# mainboard.net
KiCad netlist of a schematic drawn in Altium Designer
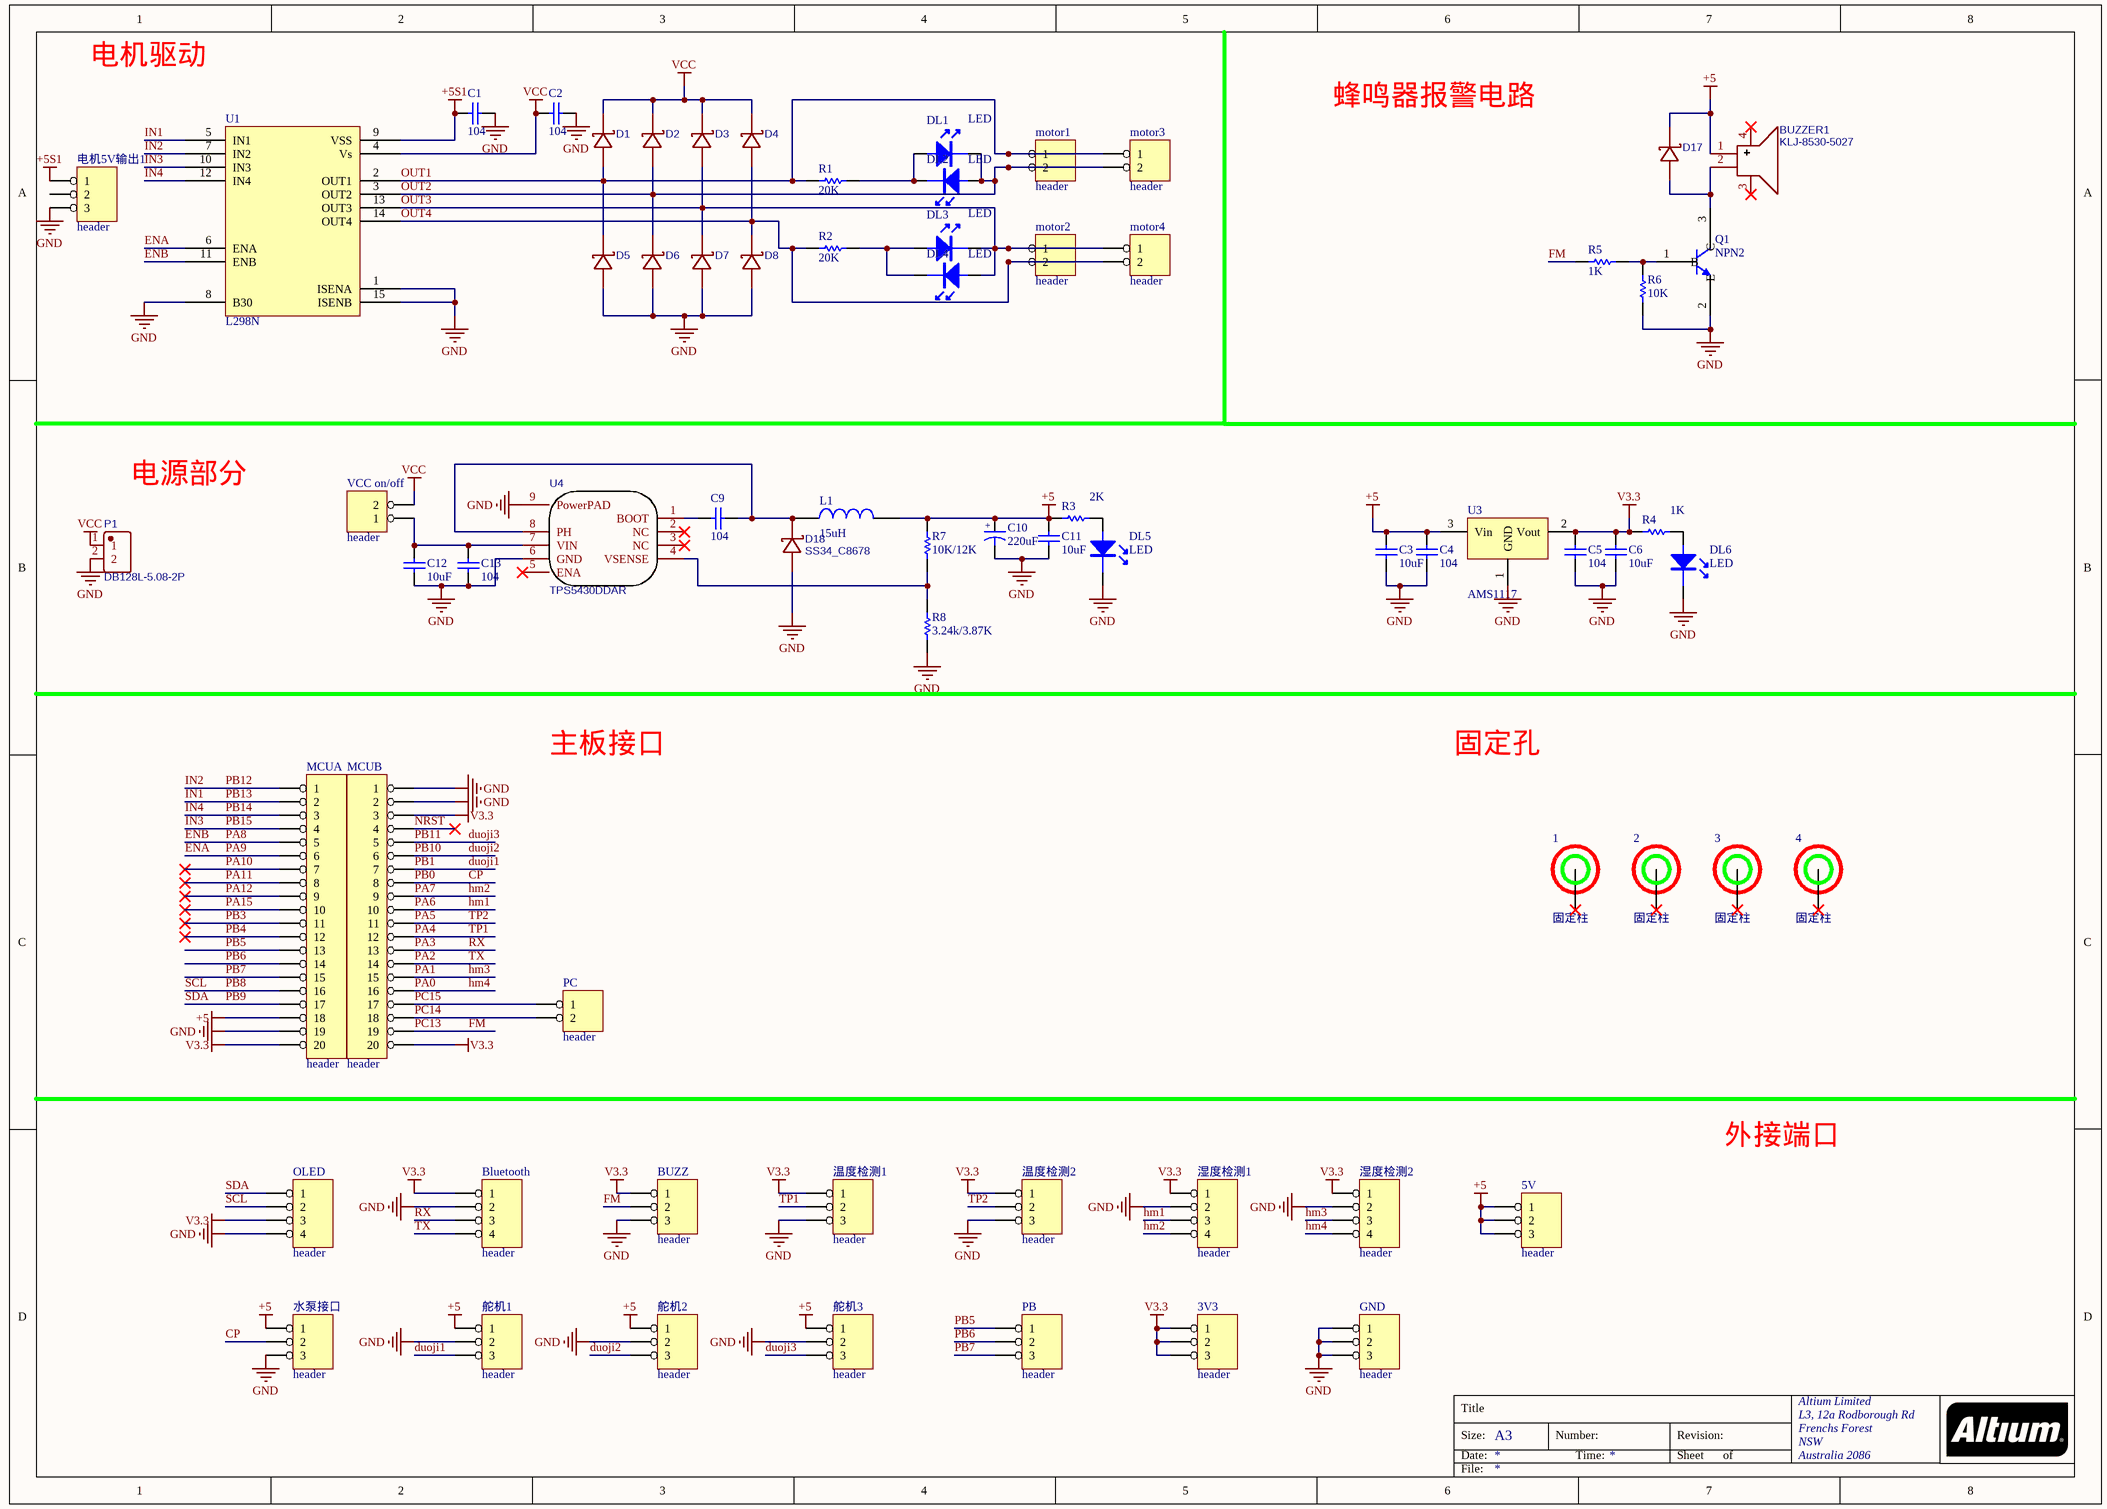
[diagram p0: mainboard.SchDoc]

(export (version "E")
  (design (tool "Eeschema 10.0.6"))
  (components
    (comp (ref "1") (value "固定柱") (footprint "M3x4+6_L") (libsource (lib "My Footprint") (part "M3*10 固定柱")))
    (comp (ref "2") (value "固定柱") (footprint "M3x4+6_L") (libsource (lib "My Footprint") (part "M3*10 固定柱")))
    (comp (ref "3") (value "固定柱") (footprint "M3x4+6_L") (libsource (lib "My Footprint") (part "M3*10 固定柱")))
    (comp (ref "3V3")
      (value "header")
      (footprint "header3")
      (libsource (lib "My Footprint") (part "HEADER 3"))
    )
    (comp (ref "4") (value "固定柱") (footprint "M3x4+6_L") (libsource (lib "My Footprint") (part "M3*10 固定柱")))
    (comp (ref "5V")
      (value "header")
      (footprint "header3")
      (libsource (lib "My Footprint") (part "HEADER 3"))
    )
    (comp (ref "Bluetooth")
      (value "header")
      (footprint "header4")
      (libsource (lib "My Footprint") (part "HEADER 4"))
    )
    (comp (ref "BUZZ")
      (value "header")
      (footprint "header3")
      (libsource (lib "My Footprint") (part "HEADER 3"))
    )
    (comp (ref "BUZZER1")
      (value "KLJ-8530-5027")
      (footprint "BUZ-SMD_4P-L8.5-W8.5-TL")
      (fields (field (name "BOM_SUPPLIER PART") "C556938") (field (name "CONTRIBUTOR") "LCSC"))
      (libsource (lib "My Footprint") (part "BUZZ"))
    )
    (comp (ref "C1")
      (value "104")
      (footprint "0603_C")
      (description "Capacitor")
      (fields (field (name "PUBLISHER") "Altium Limited"))
      (libsource (lib "My Footprint") (part "CAP"))
    )
    (comp (ref "C2")
      (value "104")
      (footprint "0603_C")
      (description "Capacitor")
      (fields (field (name "PUBLISHER") "Altium Limited"))
      (libsource (lib "My Footprint") (part "CAP"))
    )
    (comp (ref "C3")
      (value "10uF")
      (footprint "0603_C")
      (description "Capacitor")
      (fields (field (name "PUBLISHER") "Altium Limited"))
      (libsource (lib "My Footprint") (part "CAP"))
    )
    (comp (ref "C4")
      (value "104")
      (footprint "0603_C")
      (description "Capacitor")
      (fields (field (name "PUBLISHER") "Altium Limited"))
      (libsource (lib "My Footprint") (part "CAP"))
    )
    (comp (ref "C5")
      (value "104")
      (footprint "0603_C")
      (description "Capacitor")
      (fields (field (name "PUBLISHER") "Altium Limited"))
      (libsource (lib "My Footprint") (part "CAP"))
    )
    (comp (ref "C6")
      (value "10uF")
      (footprint "0603_C")
      (description "Capacitor")
      (fields (field (name "PUBLISHER") "Altium Limited"))
      (libsource (lib "My Footprint") (part "CAP"))
    )
    (comp (ref "C9")
      (value "104")
      (footprint "0603_C")
      (description "Capacitor")
      (fields (field (name "PUBLISHER") "Altium Limited"))
      (libsource (lib "My Footprint") (part "CAP"))
    )
    (comp (ref "C10") (value "220uF") (footprint "CD7") (libsource (lib "My Footprint") (part "CAP1")))
    (comp (ref "C11")
      (value "10uF")
      (footprint "0805_c")
      (description "Capacitor")
      (fields (field (name "PUBLISHER") "Altium Limited"))
      (libsource (lib "My Footprint") (part "CAP"))
    )
    (comp (ref "C12")
      (value "10uF")
      (footprint "0805_c")
      (description "Capacitor")
      (fields (field (name "PUBLISHER") "Altium Limited"))
      (libsource (lib "My Footprint") (part "CAP"))
    )
    (comp (ref "C13")
      (value "104")
      (footprint "0603_C")
      (description "Capacitor")
      (fields (field (name "PUBLISHER") "Altium Limited"))
      (libsource (lib "My Footprint") (part "CAP"))
    )
    (comp (ref "D1")
      (value "~")
      (footprint "DO-214AC_L4.3-W2.7-LS5.3-RD")
      (fields (field (name "BOM_MANUFACTURER PART") "SS34") (field (name "BOM_SUPPLIER PART") "C8678"))
      (libsource (lib "My Footprint") (part "SS34_C8678"))
    )
    (comp (ref "D2")
      (value "~")
      (footprint "DO-214AC_L4.3-W2.7-LS5.3-RD")
      (fields (field (name "BOM_MANUFACTURER PART") "SS34") (field (name "BOM_SUPPLIER PART") "C8678"))
      (libsource (lib "My Footprint") (part "SS34_C8678"))
    )
    (comp (ref "D3")
      (value "~")
      (footprint "DO-214AC_L4.3-W2.7-LS5.3-RD")
      (fields (field (name "BOM_MANUFACTURER PART") "SS34") (field (name "BOM_SUPPLIER PART") "C8678"))
      (libsource (lib "My Footprint") (part "SS34_C8678"))
    )
    (comp (ref "D4")
      (value "~")
      (footprint "DO-214AC_L4.3-W2.7-LS5.3-RD")
      (fields (field (name "BOM_MANUFACTURER PART") "SS34") (field (name "BOM_SUPPLIER PART") "C8678"))
      (libsource (lib "My Footprint") (part "SS34_C8678"))
    )
    (comp (ref "D5")
      (value "~")
      (footprint "DO-214AC_L4.3-W2.7-LS5.3-RD")
      (fields (field (name "BOM_MANUFACTURER PART") "SS34") (field (name "BOM_SUPPLIER PART") "C8678"))
      (libsource (lib "My Footprint") (part "SS34_C8678"))
    )
    (comp (ref "D6")
      (value "~")
      (footprint "DO-214AC_L4.3-W2.7-LS5.3-RD")
      (fields (field (name "BOM_MANUFACTURER PART") "SS34") (field (name "BOM_SUPPLIER PART") "C8678"))
      (libsource (lib "My Footprint") (part "SS34_C8678"))
    )
    (comp (ref "D7")
      (value "~")
      (footprint "DO-214AC_L4.3-W2.7-LS5.3-RD")
      (fields (field (name "BOM_MANUFACTURER PART") "SS34") (field (name "BOM_SUPPLIER PART") "C8678"))
      (libsource (lib "My Footprint") (part "SS34_C8678"))
    )
    (comp (ref "D8")
      (value "~")
      (footprint "DO-214AC_L4.3-W2.7-LS5.3-RD")
      (fields (field (name "BOM_MANUFACTURER PART") "SS34") (field (name "BOM_SUPPLIER PART") "C8678"))
      (libsource (lib "My Footprint") (part "SS34_C8678"))
    )
    (comp (ref "D17")
      (value "~")
      (footprint "DO-214AC_L4.3-W2.7-LS5.3-RD")
      (fields (field (name "BOM_MANUFACTURER PART") "SS34") (field (name "BOM_SUPPLIER PART") "C8678"))
      (libsource (lib "My Footprint") (part "SS34_C8678"))
    )
    (comp (ref "D18")
      (value "SS34_C8678")
      (footprint "DO-214AC_L4.3-W2.7-LS5.3-RD")
      (fields (field (name "BOM_MANUFACTURER PART") "SS34") (field (name "BOM_SUPPLIER PART") "C8678"))
      (libsource (lib "My Footprint") (part "SS34_C8678"))
    )
    (comp (ref "DL1")
      (value "LED")
      (footprint "0805_LED")
      (description "LED 发光二极管")
      (libsource (lib "My Footprint") (part "LED"))
    )
    (comp (ref "DL2")
      (value "LED")
      (footprint "0805_LED")
      (description "LED 发光二极管")
      (libsource (lib "My Footprint") (part "LED"))
    )
    (comp (ref "DL3")
      (value "LED")
      (footprint "0805_LED")
      (description "LED 发光二极管")
      (libsource (lib "My Footprint") (part "LED"))
    )
    (comp (ref "DL4")
      (value "LED")
      (footprint "0805_LED")
      (description "LED 发光二极管")
      (libsource (lib "My Footprint") (part "LED"))
    )
    (comp (ref "DL5")
      (value "LED")
      (footprint "0805_LED")
      (description "LED 发光二极管")
      (libsource (lib "My Footprint") (part "LED"))
    )
    (comp (ref "DL6")
      (value "LED")
      (footprint "0805_LED")
      (description "LED 发光二极管")
      (libsource (lib "My Footprint") (part "LED"))
    )
    (comp (ref "GND")
      (value "header")
      (footprint "header3")
      (libsource (lib "My Footprint") (part "HEADER 3"))
    )
    (comp (ref "L1")
      (value "15uH")
      (footprint "CD75")
      (description "INDUCTOR")
      (libsource (lib "电感") (part "INDUCTOR"))
    )
    (comp (ref "MCUA")
      (value "header")
      (footprint "header20")
      (libsource (lib "My Footprint") (part "HEADER 20"))
    )
    (comp (ref "MCUB") (value "header") (footprint "header20") (libsource (lib "") (part "HEADER 20_1")))
    (comp (ref "motor1")
      (value "header")
      (footprint "header2")
      (libsource (lib "My Footprint") (part "HEADER 2"))
    )
    (comp (ref "motor2")
      (value "header")
      (footprint "header2")
      (libsource (lib "My Footprint") (part "HEADER 2"))
    )
    (comp (ref "motor3")
      (value "header")
      (footprint "header2")
      (libsource (lib "My Footprint") (part "HEADER 2"))
    )
    (comp (ref "motor4")
      (value "header")
      (footprint "header2")
      (libsource (lib "My Footprint") (part "HEADER 2"))
    )
    (comp (ref "OLED")
      (value "header")
      (footprint "header4")
      (libsource (lib "My Footprint") (part "HEADER 4"))
    )
    (comp (ref "P1")
      (value "DB128L-5.08-2P")
      (footprint "CONN-TH_2P-P5.08_DB128L-5.08-2P")
      (fields (field (name "BOM_SUPPLIER PART") "C395868") (field (name "CONTRIBUTOR") "LCSC"))
      (libsource (lib "My Footprint") (part "duanzi-5.08-2P"))
    )
    (comp (ref "PB")
      (value "header")
      (footprint "header3")
      (libsource (lib "My Footprint") (part "HEADER 3"))
    )
    (comp (ref "PC")
      (value "header")
      (footprint "header2")
      (libsource (lib "My Footprint") (part "HEADER 2"))
    )
    (comp (ref "Q1")
      (value "NPN2")
      (footprint "SOT-23-3")
      (description "贴片")
      (libsource (lib "My Footprint") (part "NPN2"))
    )
    (comp (ref "R1")
      (value "20K")
      (footprint "0603_R")
      (description "Resistor")
      (fields (field (name "PUBLISHER") "Altium Limited"))
      (libsource (lib "My Footprint") (part "RES"))
    )
    (comp (ref "R2")
      (value "20K")
      (footprint "0603_R")
      (description "Resistor")
      (fields (field (name "PUBLISHER") "Altium Limited"))
      (libsource (lib "My Footprint") (part "RES"))
    )
    (comp (ref "R3")
      (value "2K")
      (footprint "0805_r")
      (description "Resistor")
      (fields (field (name "PUBLISHER") "Altium Limited"))
      (libsource (lib "My Footprint") (part "RES"))
    )
    (comp (ref "R4")
      (value "1K")
      (footprint "0805_r")
      (description "Resistor")
      (fields (field (name "PUBLISHER") "Altium Limited"))
      (libsource (lib "My Footprint") (part "RES"))
    )
    (comp (ref "R5")
      (value "1K")
      (footprint "0805_r")
      (description "Resistor")
      (fields (field (name "PUBLISHER") "Altium Limited"))
      (libsource (lib "My Footprint") (part "RES"))
    )
    (comp (ref "R6")
      (value "10K")
      (footprint "0805_r")
      (description "Resistor")
      (fields (field (name "PUBLISHER") "Altium Limited"))
      (libsource (lib "My Footprint") (part "RES"))
    )
    (comp (ref "R7")
      (value "10K/12K")
      (footprint "0805_r")
      (description "Resistor")
      (fields (field (name "PUBLISHER") "Altium Limited"))
      (libsource (lib "My Footprint") (part "RES"))
    )
    (comp (ref "R8")
      (value "3.24k/3.87K")
      (footprint "0805_r")
      (description "Resistor")
      (fields (field (name "PUBLISHER") "Altium Limited"))
      (libsource (lib "My Footprint") (part "RES"))
    )
    (comp (ref "U1") (value "L298N") (footprint "L298N") (libsource (lib "My Footprint") (part "L298N")))
    (comp (ref "U3")
      (value "AMS1117")
      (footprint "SOT-223")
      (description "3.3V电压转换器AMS1117")
      (libsource (lib "My Footprint") (part "AMS1117"))
    )
    (comp (ref "U4")
      (value "TPS5430DDAR")
      (footprint "SOIC-8_L5.0-W4.0-P1.27-LS6.0-BL-EP")
      (fields (field (name "BOM_SUPPLIER PART") "C9864"))
      (libsource (lib "My Footprint") (part "TPS5430DDAR"))
    )
    (comp (ref "VCC on/off") (value "header") (footprint "header2") (libsource (lib "") (part "HEADER 2_1")))
    (comp (ref "水泵接口")
      (value "header")
      (footprint "header3")
      (libsource (lib "My Footprint") (part "HEADER 3"))
    )
    (comp (ref "温度检测1")
      (value "header")
      (footprint "header3")
      (libsource (lib "My Footprint") (part "HEADER 3"))
    )
    (comp (ref "温度检测2")
      (value "header")
      (footprint "header3")
      (libsource (lib "My Footprint") (part "HEADER 3"))
    )
    (comp (ref "湿度检测1")
      (value "header")
      (footprint "header4")
      (libsource (lib "My Footprint") (part "HEADER 4"))
    )
    (comp (ref "湿度检测2")
      (value "header")
      (footprint "header4")
      (libsource (lib "My Footprint") (part "HEADER 4"))
    )
    (comp (ref "电机5V输出1")
      (value "header")
      (footprint "header3")
      (libsource (lib "My Footprint") (part "HEADER 3"))
    )
    (comp (ref "舵机1")
      (value "header")
      (footprint "header3")
      (libsource (lib "My Footprint") (part "HEADER 3"))
    )
    (comp (ref "舵机2")
      (value "header")
      (footprint "header3")
      (libsource (lib "My Footprint") (part "HEADER 3"))
    )
    (comp (ref "舵机3")
      (value "header")
      (footprint "header3")
      (libsource (lib "My Footprint") (part "HEADER 3"))
    )
  )
  (nets
    (net (code "1") (name "+5") (class "Default")
      (node (ref "5V") (pin "1") (pinfunction "1_1") (pintype "passive"))
      (node (ref "5V") (pin "2") (pinfunction "2_2") (pintype "passive"))
      (node (ref "5V") (pin "3") (pinfunction "3_3") (pintype "passive"))
      (node (ref "BUZZER1") (pin "1") (pinfunction "+_1") (pintype "passive"))
      (node (ref "C10") (pin "1") (pinfunction "1_1") (pintype "passive"))
      (node (ref "C11") (pin "2") (pinfunction "2_2") (pintype "passive"))
      (node (ref "C3") (pin "2") (pinfunction "2_2") (pintype "passive"))
      (node (ref "C4") (pin "2") (pinfunction "2_2") (pintype "passive"))
      (node (ref "D17") (pin "1") (pinfunction "K_1") (pintype "passive"))
      (node (ref "L1") (pin "2") (pinfunction "2_2") (pintype "passive"))
      (node (ref "MCUA") (pin "18") (pinfunction "18_18") (pintype "passive"))
      (node (ref "R3") (pin "2") (pinfunction "2_2") (pintype "passive"))
      (node (ref "R7") (pin "2") (pinfunction "2_2") (pintype "passive"))
      (node (ref "U3") (pin "3") (pinfunction "Vin_3") (pintype "passive"))
      (node (ref "水泵接口") (pin "1") (pinfunction "1_1") (pintype "passive"))
      (node (ref "舵机1") (pin "1") (pinfunction "1_1") (pintype "passive"))
      (node (ref "舵机2") (pin "1") (pinfunction "1_1") (pintype "passive"))
      (node (ref "舵机3") (pin "1") (pinfunction "1_1") (pintype "passive"))
    )
    (net (code "2") (name "+5S1") (class "Default")
      (node (ref "C1") (pin "1") (pinfunction "1_1") (pintype "passive"))
      (node (ref "U1") (pin "9") (pinfunction "VSS_9") (pintype "passive"))
      (node (ref "电机5V输出1") (pin "1") (pinfunction "1_1") (pintype "passive"))
    )
    (net (code "3") (name "/CP") (class "Default")
      (node (ref "MCUB") (pin "8") (pinfunction "8_8") (pintype "passive"))
      (node (ref "水泵接口") (pin "2") (pinfunction "2_2") (pintype "passive"))
    )
    (net (code "4") (name "/ENA") (class "Default")
      (node (ref "MCUA") (pin "6") (pinfunction "6_6") (pintype "passive"))
      (node (ref "U1") (pin "6") (pinfunction "ENA_6") (pintype "passive"))
    )
    (net (code "5") (name "/ENB") (class "Default")
      (node (ref "MCUA") (pin "5") (pinfunction "5_5") (pintype "passive"))
      (node (ref "U1") (pin "11") (pinfunction "ENB_11") (pintype "passive"))
    )
    (net (code "6") (name "/FM") (class "Default")
      (node (ref "BUZZ") (pin "2") (pinfunction "2_2") (pintype "passive"))
      (node (ref "MCUB") (pin "19") (pinfunction "19_19") (pintype "passive"))
      (node (ref "R5") (pin "1") (pinfunction "1_1") (pintype "passive"))
    )
    (net (code "7") (name "/IN1") (class "Default")
      (node (ref "MCUA") (pin "2") (pinfunction "2_2") (pintype "passive"))
      (node (ref "U1") (pin "5") (pinfunction "IN1_5") (pintype "passive"))
    )
    (net (code "8") (name "/IN2") (class "Default")
      (node (ref "MCUA") (pin "1") (pinfunction "1_1") (pintype "passive"))
      (node (ref "U1") (pin "7") (pinfunction "IN2_7") (pintype "passive"))
    )
    (net (code "9") (name "/IN3") (class "Default")
      (node (ref "MCUA") (pin "4") (pinfunction "4_4") (pintype "passive"))
      (node (ref "U1") (pin "10") (pinfunction "IN3_10") (pintype "passive"))
    )
    (net (code "10") (name "/IN4") (class "Default")
      (node (ref "MCUA") (pin "3") (pinfunction "3_3") (pintype "passive"))
      (node (ref "U1") (pin "12") (pinfunction "IN4_12") (pintype "passive"))
    )
    (net (code "11") (name "/NRST") (class "Default")
      (node (ref "MCUB") (pin "4") (pinfunction "4_4") (pintype "passive+no_connect"))
    )
    (net (code "12") (name "/OUT1") (class "Default")
      (node (ref "D1") (pin "2") (pinfunction "A_2") (pintype "passive"))
      (node (ref "D5") (pin "1") (pinfunction "K_1") (pintype "passive"))
      (node (ref "R1") (pin "1") (pinfunction "1_1") (pintype "passive"))
      (node (ref "U1") (pin "2") (pinfunction "OUT1_2") (pintype "passive"))
      (node (ref "motor1") (pin "1") (pinfunction "1_1") (pintype "passive"))
      (node (ref "motor3") (pin "1") (pinfunction "1_1") (pintype "passive"))
    )
    (net (code "13") (name "/OUT2") (class "Default")
      (node (ref "D2") (pin "2") (pinfunction "A_2") (pintype "passive"))
      (node (ref "D6") (pin "1") (pinfunction "K_1") (pintype "passive"))
      (node (ref "DL1") (pin "2") (pinfunction "K_2") (pintype "passive"))
      (node (ref "DL2") (pin "1") (pinfunction "A_1") (pintype "passive"))
      (node (ref "U1") (pin "3") (pinfunction "OUT2_3") (pintype "passive"))
      (node (ref "motor1") (pin "2") (pinfunction "2_2") (pintype "passive"))
      (node (ref "motor3") (pin "2") (pinfunction "2_2") (pintype "passive"))
    )
    (net (code "14") (name "/OUT3") (class "Default")
      (node (ref "D3") (pin "2") (pinfunction "A_2") (pintype "passive"))
      (node (ref "D7") (pin "1") (pinfunction "K_1") (pintype "passive"))
      (node (ref "DL3") (pin "2") (pinfunction "K_2") (pintype "passive"))
      (node (ref "DL4") (pin "1") (pinfunction "A_1") (pintype "passive"))
      (node (ref "U1") (pin "13") (pinfunction "OUT3_13") (pintype "passive"))
      (node (ref "motor2") (pin "1") (pinfunction "1_1") (pintype "passive"))
      (node (ref "motor4") (pin "1") (pinfunction "1_1") (pintype "passive"))
    )
    (net (code "15") (name "/OUT4") (class "Default")
      (node (ref "D4") (pin "2") (pinfunction "A_2") (pintype "passive"))
      (node (ref "D8") (pin "1") (pinfunction "K_1") (pintype "passive"))
      (node (ref "R2") (pin "1") (pinfunction "1_1") (pintype "passive"))
      (node (ref "U1") (pin "14") (pinfunction "OUT4_14") (pintype "passive"))
      (node (ref "motor2") (pin "2") (pinfunction "2_2") (pintype "passive"))
      (node (ref "motor4") (pin "2") (pinfunction "2_2") (pintype "passive"))
    )
    (net (code "16") (name "/PA0") (class "Default")
      (node (ref "MCUB") (pin "16") (pinfunction "16_16") (pintype "passive"))
      (node (ref "湿度检测2") (pin "4") (pinfunction "4_4") (pintype "passive"))
    )
    (net (code "17") (name "/PA1") (class "Default")
      (node (ref "MCUB") (pin "15") (pinfunction "15_15") (pintype "passive"))
      (node (ref "湿度检测2") (pin "3") (pinfunction "3_3") (pintype "passive"))
    )
    (net (code "18") (name "/PA2") (class "Default")
      (node (ref "Bluetooth") (pin "4") (pinfunction "4_4") (pintype "passive"))
      (node (ref "MCUB") (pin "14") (pinfunction "14_14") (pintype "passive"))
    )
    (net (code "19") (name "/PA3") (class "Default")
      (node (ref "Bluetooth") (pin "3") (pinfunction "3_3") (pintype "passive"))
      (node (ref "MCUB") (pin "13") (pinfunction "13_13") (pintype "passive"))
    )
    (net (code "20") (name "/PA4") (class "Default")
      (node (ref "MCUB") (pin "12") (pinfunction "12_12") (pintype "passive"))
      (node (ref "温度检测1") (pin "2") (pinfunction "2_2") (pintype "passive"))
    )
    (net (code "21") (name "/PA5") (class "Default")
      (node (ref "MCUB") (pin "11") (pinfunction "11_11") (pintype "passive"))
      (node (ref "温度检测2") (pin "2") (pinfunction "2_2") (pintype "passive"))
    )
    (net (code "22") (name "/PA6") (class "Default")
      (node (ref "MCUB") (pin "10") (pinfunction "10_10") (pintype "passive"))
      (node (ref "湿度检测1") (pin "3") (pinfunction "3_3") (pintype "passive"))
    )
    (net (code "23") (name "/PA7") (class "Default")
      (node (ref "MCUB") (pin "9") (pinfunction "9_9") (pintype "passive"))
      (node (ref "湿度检测1") (pin "4") (pinfunction "4_4") (pintype "passive"))
    )
    (net (code "24") (name "/PA10") (class "Default")
      (node (ref "MCUA") (pin "7") (pinfunction "7_7") (pintype "passive+no_connect"))
    )
    (net (code "25") (name "/PA11") (class "Default")
      (node (ref "MCUA") (pin "8") (pinfunction "8_8") (pintype "passive+no_connect"))
    )
    (net (code "26") (name "/PA12") (class "Default")
      (node (ref "MCUA") (pin "9") (pinfunction "9_9") (pintype "passive+no_connect"))
    )
    (net (code "27") (name "/PA15") (class "Default")
      (node (ref "MCUA") (pin "10") (pinfunction "10_10") (pintype "passive+no_connect"))
    )
    (net (code "28") (name "/PB1") (class "Default")
      (node (ref "MCUB") (pin "7") (pinfunction "7_7") (pintype "passive"))
      (node (ref "舵机1") (pin "3") (pinfunction "3_3") (pintype "passive"))
    )
    (net (code "29") (name "/PB3") (class "Default")
      (node (ref "MCUA") (pin "11") (pinfunction "11_11") (pintype "passive+no_connect"))
    )
    (net (code "30") (name "/PB4") (class "Default")
      (node (ref "MCUA") (pin "12") (pinfunction "12_12") (pintype "passive+no_connect"))
    )
    (net (code "31") (name "/PB5") (class "Default")
      (node (ref "MCUA") (pin "13") (pinfunction "13_13") (pintype "passive"))
      (node (ref "PB") (pin "1") (pinfunction "1_1") (pintype "passive"))
    )
    (net (code "32") (name "/PB6") (class "Default")
      (node (ref "MCUA") (pin "14") (pinfunction "14_14") (pintype "passive"))
      (node (ref "PB") (pin "2") (pinfunction "2_2") (pintype "passive"))
    )
    (net (code "33") (name "/PB7") (class "Default")
      (node (ref "MCUA") (pin "15") (pinfunction "15_15") (pintype "passive"))
      (node (ref "PB") (pin "3") (pinfunction "3_3") (pintype "passive"))
    )
    (net (code "34") (name "/PB8") (class "Default")
      (node (ref "MCUA") (pin "16") (pinfunction "16_16") (pintype "passive"))
      (node (ref "OLED") (pin "2") (pinfunction "2_2") (pintype "passive"))
    )
    (net (code "35") (name "/PB9") (class "Default")
      (node (ref "MCUA") (pin "17") (pinfunction "17_17") (pintype "passive"))
      (node (ref "OLED") (pin "1") (pinfunction "1_1") (pintype "passive"))
    )
    (net (code "36") (name "/PB10") (class "Default")
      (node (ref "MCUB") (pin "6") (pinfunction "6_6") (pintype "passive"))
      (node (ref "舵机2") (pin "3") (pinfunction "3_3") (pintype "passive"))
    )
    (net (code "37") (name "/PB11") (class "Default")
      (node (ref "MCUB") (pin "5") (pinfunction "5_5") (pintype "passive"))
      (node (ref "舵机3") (pin "3") (pinfunction "3_3") (pintype "passive"))
    )
    (net (code "38") (name "/PC14") (class "Default")
      (node (ref "MCUB") (pin "18") (pinfunction "18_18") (pintype "passive"))
      (node (ref "PC") (pin "2") (pinfunction "2_2") (pintype "passive"))
    )
    (net (code "39") (name "/PC15") (class "Default")
      (node (ref "MCUB") (pin "17") (pinfunction "17_17") (pintype "passive"))
      (node (ref "PC") (pin "1") (pinfunction "1_1") (pintype "passive"))
    )
    (net (code "40") (name "GND") (class "Default")
      (node (ref "BUZZ") (pin "3") (pinfunction "3_3") (pintype "passive"))
      (node (ref "Bluetooth") (pin "2") (pinfunction "2_2") (pintype "passive"))
      (node (ref "C1") (pin "2") (pinfunction "2_2") (pintype "passive"))
      (node (ref "C10") (pin "2") (pinfunction "2_2") (pintype "passive"))
      (node (ref "C11") (pin "1") (pinfunction "1_1") (pintype "passive"))
      (node (ref "C12") (pin "1") (pinfunction "1_1") (pintype "passive"))
      (node (ref "C13") (pin "1") (pinfunction "1_1") (pintype "passive"))
      (node (ref "C2") (pin "2") (pinfunction "2_2") (pintype "passive"))
      (node (ref "C3") (pin "1") (pinfunction "1_1") (pintype "passive"))
      (node (ref "C4") (pin "1") (pinfunction "1_1") (pintype "passive"))
      (node (ref "C5") (pin "1") (pinfunction "1_1") (pintype "passive"))
      (node (ref "C6") (pin "1") (pinfunction "1_1") (pintype "passive"))
      (node (ref "D18") (pin "2") (pinfunction "A_2") (pintype "passive"))
      (node (ref "D5") (pin "2") (pinfunction "A_2") (pintype "passive"))
      (node (ref "D6") (pin "2") (pinfunction "A_2") (pintype "passive"))
      (node (ref "D7") (pin "2") (pinfunction "A_2") (pintype "passive"))
      (node (ref "D8") (pin "2") (pinfunction "A_2") (pintype "passive"))
      (node (ref "DL5") (pin "2") (pinfunction "K_2") (pintype "passive"))
      (node (ref "DL6") (pin "2") (pinfunction "K_2") (pintype "passive"))
      (node (ref "GND") (pin "1") (pinfunction "1_1") (pintype "passive"))
      (node (ref "GND") (pin "2") (pinfunction "2_2") (pintype "passive"))
      (node (ref "GND") (pin "3") (pinfunction "3_3") (pintype "passive"))
      (node (ref "MCUA") (pin "19") (pinfunction "19_19") (pintype "passive"))
      (node (ref "MCUB") (pin "1") (pinfunction "1_1") (pintype "passive"))
      (node (ref "MCUB") (pin "2") (pinfunction "2_2") (pintype "passive"))
      (node (ref "OLED") (pin "4") (pinfunction "4_4") (pintype "passive"))
      (node (ref "P1") (pin "2") (pinfunction "2_2") (pintype "passive"))
      (node (ref "Q1") (pin "2") (pinfunction "E_2") (pintype "passive"))
      (node (ref "R6") (pin "1") (pinfunction "1_1") (pintype "passive"))
      (node (ref "R8") (pin "1") (pinfunction "1_1") (pintype "passive"))
      (node (ref "U1") (pin "1") (pinfunction "ISENA_1") (pintype "passive"))
      (node (ref "U1") (pin "15") (pinfunction "ISENB_15") (pintype "passive"))
      (node (ref "U1") (pin "8") (pinfunction "B30_8") (pintype "passive"))
      (node (ref "U3") (pin "1") (pinfunction "GND_1") (pintype "passive"))
      (node (ref "U4") (pin "6") (pinfunction "GND_6") (pintype "passive"))
      (node (ref "U4") (pin "9") (pinfunction "PowerPAD_9") (pintype "passive"))
      (node (ref "水泵接口") (pin "3") (pinfunction "3_3") (pintype "passive"))
      (node (ref "温度检测1") (pin "3") (pinfunction "3_3") (pintype "passive"))
      (node (ref "温度检测2") (pin "3") (pinfunction "3_3") (pintype "passive"))
      (node (ref "湿度检测1") (pin "2") (pinfunction "2_2") (pintype "passive"))
      (node (ref "湿度检测2") (pin "2") (pinfunction "2_2") (pintype "passive"))
      (node (ref "电机5V输出1") (pin "3") (pinfunction "3_3") (pintype "passive"))
      (node (ref "舵机1") (pin "2") (pinfunction "2_2") (pintype "passive"))
      (node (ref "舵机2") (pin "2") (pinfunction "2_2") (pintype "passive"))
      (node (ref "舵机3") (pin "2") (pinfunction "2_2") (pintype "passive"))
    )
    (net (code "41") (name "Net-(BUZZER1--)") (class "Default")
      (node (ref "BUZZER1") (pin "2") (pinfunction "-_2") (pintype "passive"))
      (node (ref "D17") (pin "2") (pinfunction "A_2") (pintype "passive"))
      (node (ref "Q1") (pin "3") (pinfunction "C_3") (pintype "passive"))
    )
    (net (code "42") (name "Net-(D18-K)") (class "Default")
      (node (ref "C9") (pin "1") (pinfunction "1_1") (pintype "passive"))
      (node (ref "D18") (pin "1") (pinfunction "K_1") (pintype "passive"))
      (node (ref "L1") (pin "1") (pinfunction "1_1") (pintype "passive"))
      (node (ref "U4") (pin "8") (pinfunction "PH_8") (pintype "passive"))
    )
    (net (code "43") (name "Net-(DL1-A)") (class "Default")
      (node (ref "DL1") (pin "1") (pinfunction "A_1") (pintype "passive"))
      (node (ref "DL2") (pin "2") (pinfunction "K_2") (pintype "passive"))
      (node (ref "R1") (pin "2") (pinfunction "2_2") (pintype "passive"))
    )
    (net (code "44") (name "Net-(DL3-A)") (class "Default")
      (node (ref "DL3") (pin "1") (pinfunction "A_1") (pintype "passive"))
      (node (ref "DL4") (pin "2") (pinfunction "K_2") (pintype "passive"))
      (node (ref "R2") (pin "2") (pinfunction "2_2") (pintype "passive"))
    )
    (net (code "45") (name "Net-(DL5-A)") (class "Default")
      (node (ref "DL5") (pin "1") (pinfunction "A_1") (pintype "passive"))
      (node (ref "R3") (pin "1") (pinfunction "1_1") (pintype "passive"))
    )
    (net (code "46") (name "Net-(DL6-A)") (class "Default")
      (node (ref "DL6") (pin "1") (pinfunction "A_1") (pintype "passive"))
      (node (ref "R4") (pin "1") (pinfunction "1_1") (pintype "passive"))
    )
    (net (code "47") (name "Net-(Q1-B)") (class "Default")
      (node (ref "Q1") (pin "1") (pinfunction "B_1") (pintype "passive"))
      (node (ref "R5") (pin "2") (pinfunction "2_2") (pintype "passive"))
      (node (ref "R6") (pin "2") (pinfunction "2_2") (pintype "passive"))
    )
    (net (code "48") (name "Net-(U4-BOOT)") (class "Default")
      (node (ref "C9") (pin "2") (pinfunction "2_2") (pintype "passive"))
      (node (ref "U4") (pin "1") (pinfunction "BOOT_1") (pintype "passive"))
    )
    (net (code "49") (name "Net-(U4-VIN)") (class "Default")
      (node (ref "C12") (pin "2") (pinfunction "2_2") (pintype "passive"))
      (node (ref "C13") (pin "2") (pinfunction "2_2") (pintype "passive"))
      (node (ref "U4") (pin "7") (pinfunction "VIN_7") (pintype "passive"))
      (node (ref "VCC on/off") (pin "1") (pinfunction "1_1") (pintype "passive"))
    )
    (net (code "50") (name "Net-(U4-VSENSE)") (class "Default")
      (node (ref "R7") (pin "1") (pinfunction "1_1") (pintype "passive"))
      (node (ref "R8") (pin "2") (pinfunction "2_2") (pintype "passive"))
      (node (ref "U4") (pin "4") (pinfunction "VSENSE_4") (pintype "passive"))
    )
    (net (code "51") (name "V3.3") (class "Default")
      (node (ref "3V3") (pin "1") (pinfunction "1_1") (pintype "passive"))
      (node (ref "3V3") (pin "2") (pinfunction "2_2") (pintype "passive"))
      (node (ref "3V3") (pin "3") (pinfunction "3_3") (pintype "passive"))
      (node (ref "BUZZ") (pin "1") (pinfunction "1_1") (pintype "passive"))
      (node (ref "Bluetooth") (pin "1") (pinfunction "1_1") (pintype "passive"))
      (node (ref "C5") (pin "2") (pinfunction "2_2") (pintype "passive"))
      (node (ref "C6") (pin "2") (pinfunction "2_2") (pintype "passive"))
      (node (ref "MCUA") (pin "20") (pinfunction "20_20") (pintype "passive"))
      (node (ref "MCUB") (pin "20") (pinfunction "20_20") (pintype "passive"))
      (node (ref "MCUB") (pin "3") (pinfunction "3_3") (pintype "passive"))
      (node (ref "OLED") (pin "3") (pinfunction "3_3") (pintype "passive"))
      (node (ref "R4") (pin "2") (pinfunction "2_2") (pintype "passive"))
      (node (ref "U3") (pin "2") (pinfunction "Vout_2") (pintype "passive"))
      (node (ref "温度检测1") (pin "1") (pinfunction "1_1") (pintype "passive"))
      (node (ref "温度检测2") (pin "1") (pinfunction "1_1") (pintype "passive"))
      (node (ref "湿度检测1") (pin "1") (pinfunction "1_1") (pintype "passive"))
      (node (ref "湿度检测2") (pin "1") (pinfunction "1_1") (pintype "passive"))
    )
    (net (code "52") (name "VCC") (class "Default")
      (node (ref "C2") (pin "1") (pinfunction "1_1") (pintype "passive"))
      (node (ref "D1") (pin "1") (pinfunction "K_1") (pintype "passive"))
      (node (ref "D2") (pin "1") (pinfunction "K_1") (pintype "passive"))
      (node (ref "D3") (pin "1") (pinfunction "K_1") (pintype "passive"))
      (node (ref "D4") (pin "1") (pinfunction "K_1") (pintype "passive"))
      (node (ref "P1") (pin "1") (pinfunction "1_1") (pintype "passive"))
      (node (ref "U1") (pin "4") (pinfunction "Vs_4") (pintype "passive"))
      (node (ref "VCC on/off") (pin "2") (pinfunction "2_2") (pintype "passive"))
    )
    (net (code "53") (name "unconnected-(1-Pad1)") (class "Default")
      (node (ref "1") (pin "1") (pinfunction "1_1") (pintype "passive+no_connect"))
    )
    (net (code "54") (name "unconnected-(2-Pad1)") (class "Default")
      (node (ref "2") (pin "1") (pinfunction "1_1") (pintype "passive+no_connect"))
    )
    (net (code "55") (name "unconnected-(3-Pad1)") (class "Default")
      (node (ref "3") (pin "1") (pinfunction "1_1") (pintype "passive+no_connect"))
    )
    (net (code "56") (name "unconnected-(4-Pad1)") (class "Default")
      (node (ref "4") (pin "1") (pinfunction "1_1") (pintype "passive+no_connect"))
    )
    (net (code "57") (name "unconnected-(BUZZER1-NC-Pad3)") (class "Default")
      (node (ref "BUZZER1") (pin "3") (pinfunction "NC_3") (pintype "passive+no_connect"))
    )
    (net (code "58") (name "unconnected-(BUZZER1-NC-Pad4)") (class "Default")
      (node (ref "BUZZER1") (pin "4") (pinfunction "NC_4") (pintype "passive+no_connect"))
    )
    (net (code "59") (name "unconnected-(U4-ENA-Pad5)") (class "Default")
      (node (ref "U4") (pin "5") (pinfunction "ENA_5") (pintype "passive+no_connect"))
    )
    (net (code "60") (name "unconnected-(U4-NC-Pad2)") (class "Default")
      (node (ref "U4") (pin "2") (pinfunction "NC_2") (pintype "passive+no_connect"))
    )
    (net (code "61") (name "unconnected-(U4-NC-Pad3)") (class "Default")
      (node (ref "U4") (pin "3") (pinfunction "NC_3") (pintype "passive+no_connect"))
    )
    (net (code "62") (name "unconnected-(电机5V输出1-Pad2)") (class "Default")
      (node (ref "电机5V输出1") (pin "2") (pinfunction "2_2") (pintype "passive"))
    )
  )
)
